# EE311_Example_Boost_Sch.net
KiCad netlist of a schematic drawn in Altium Designer
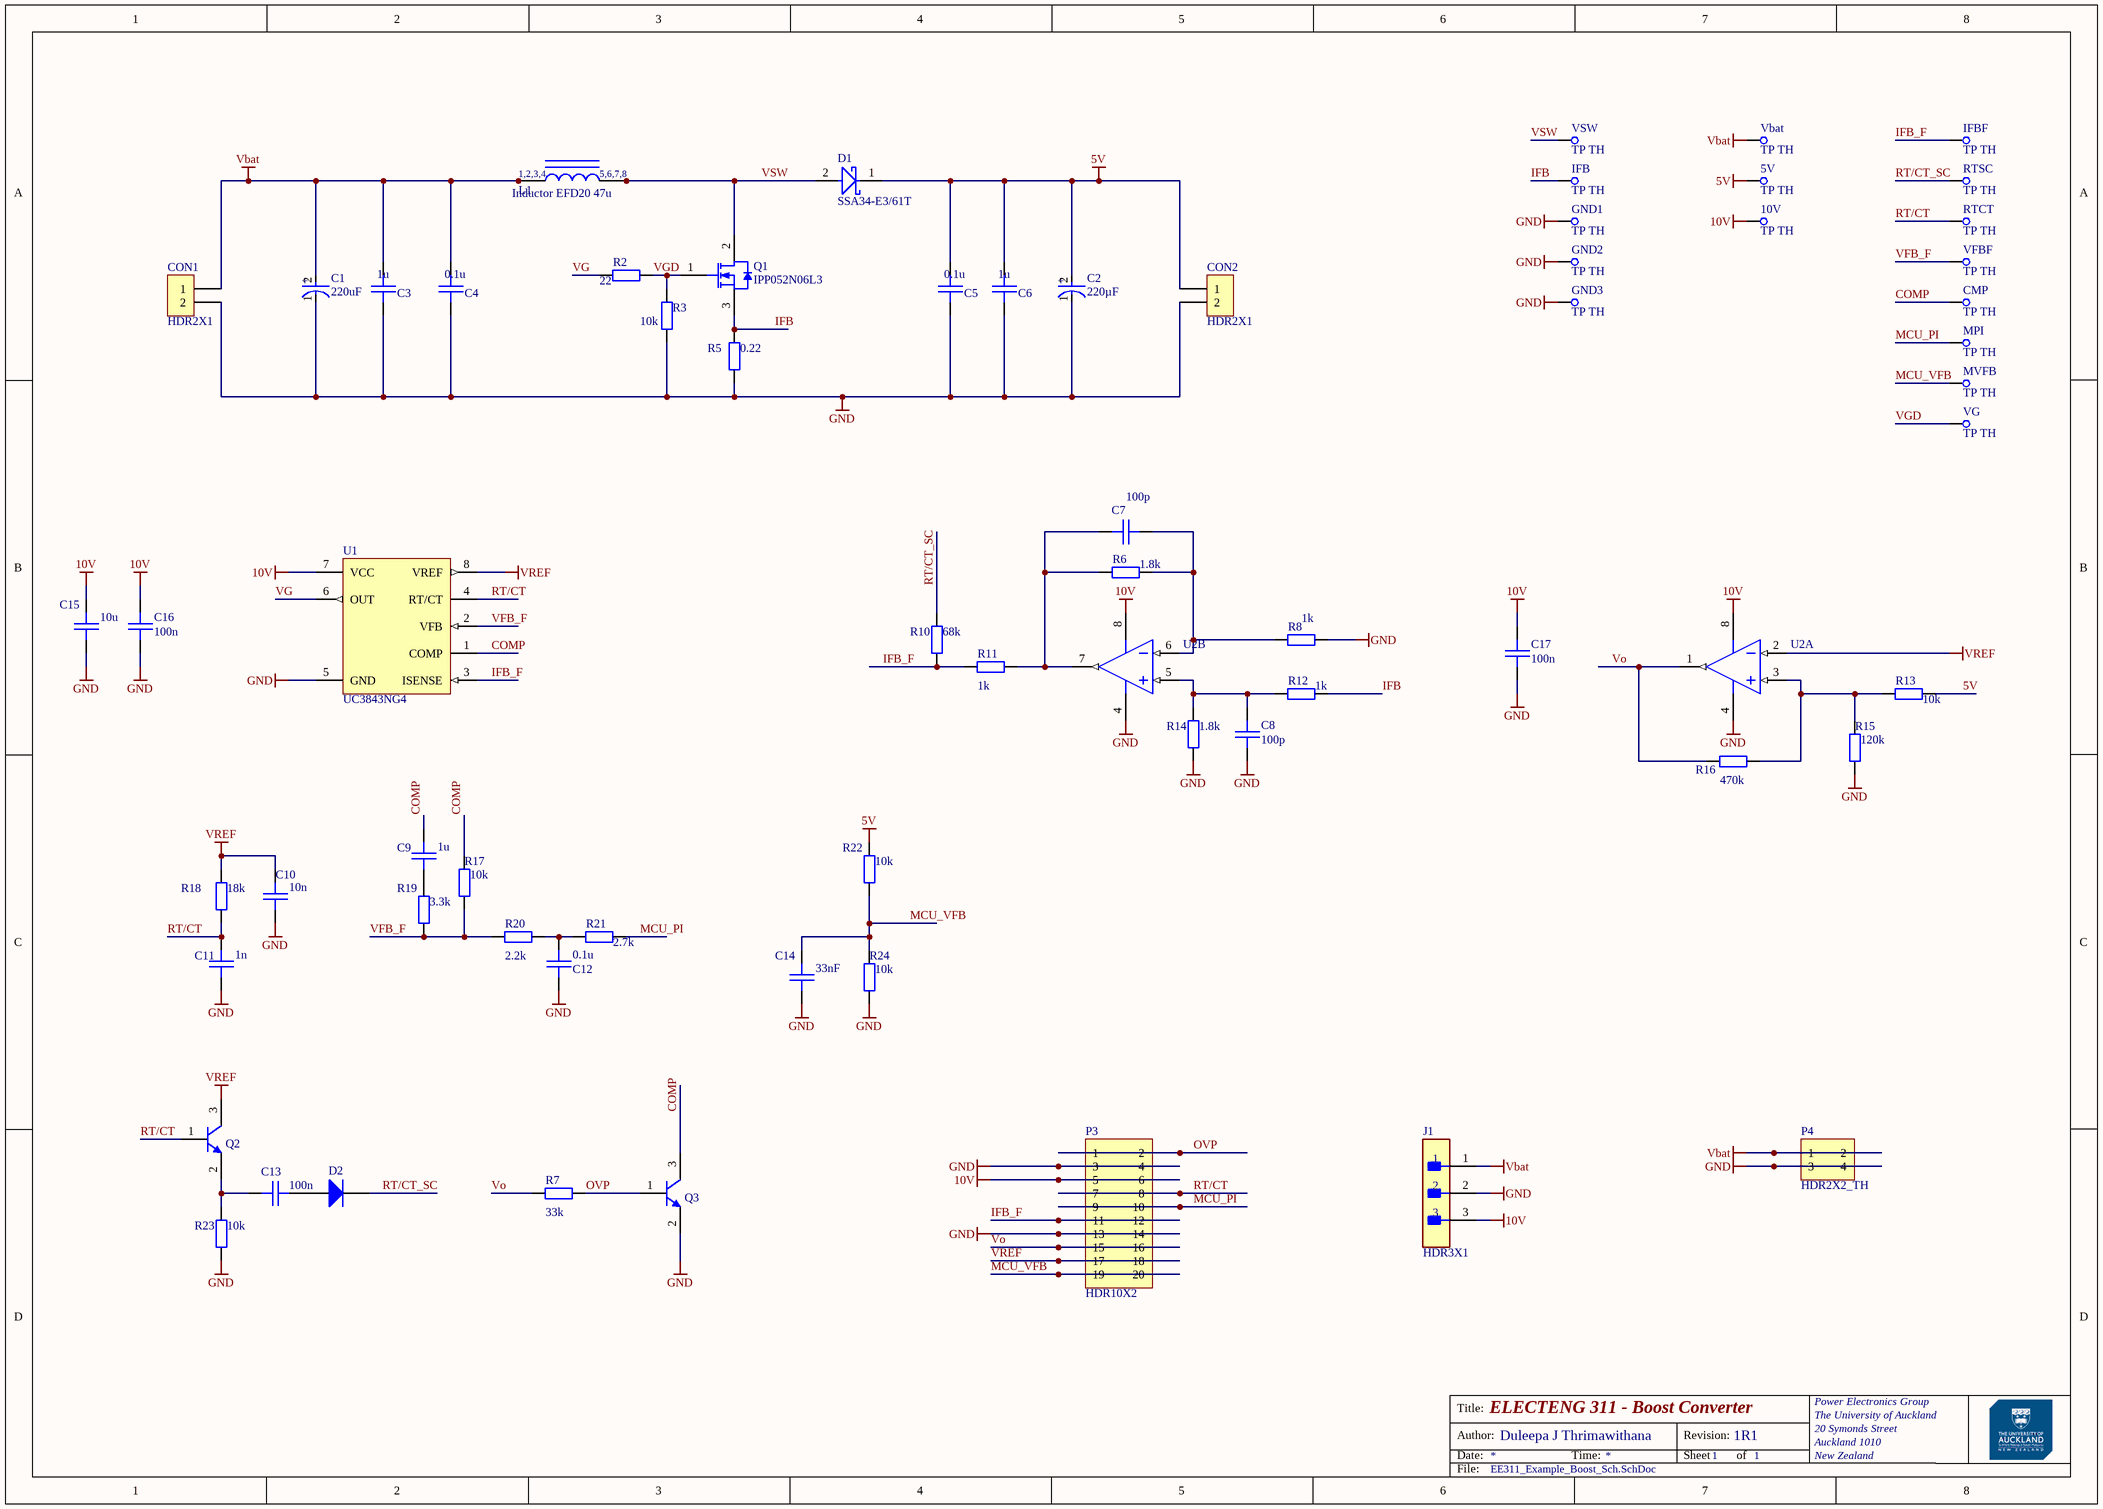
[diagram p0: EE311_Example_Boost_Sch.SchDoc]

(export (version "E")
  (design (tool "Eeschema 10.0.6"))
  (components
    (comp (ref "5V") (value "TP TH") (footprint "TP_TH_2.5mm") (libsource (lib "ECSE@UoA") (part "TP TH")))
    (comp (ref "10V") (value "TP TH") (footprint "TP_TH_2.5mm") (libsource (lib "ECSE@UoA") (part "TP TH")))
    (comp (ref "C1")
      (value "220uF")
      (footprint "FP-FKF-MFG")
      (fields (field (name "Comment") "EEE-FK1K330P"))
      (libsource (lib "ECSE@UoA") (part "a00bbbee19879c290e62620ae7e47b1"))
    )
    (comp (ref "C2")
      (value "220µF")
      (footprint "FP-FKF-MFG")
      (fields (field (name "Comment") "EEE-FK1K330P"))
      (libsource (lib "ECSE@UoA") (part "a00bbbee19879c290e62620ae7e47b1"))
    )
    (comp (ref "C3")
      (value "1u")
      (footprint "C1210")
      (description "Capacitor 1210")
      (libsource (lib "") (part "Symbol_1"))
    )
    (comp (ref "C4")
      (value "0.1u")
      (footprint "C1210")
      (description "Capacitor 1210")
      (libsource (lib "") (part "Symbol_1"))
    )
    (comp (ref "C5")
      (value "0.1u")
      (footprint "C1210")
      (description "Capacitor 1210")
      (libsource (lib "") (part "Symbol_1"))
    )
    (comp (ref "C6")
      (value "1u")
      (footprint "C1210")
      (description "Capacitor 1210")
      (libsource (lib "") (part "Symbol_1"))
    )
    (comp (ref "C7")
      (value "100p")
      (footprint "C0805")
      (description "Capacitor 0805")
      (fields (field (name "Comment") "CCAP0805"))
      (libsource (lib "") (part "Symbol_1"))
    )
    (comp (ref "C8")
      (value "100p")
      (footprint "C0805")
      (description "Capacitor 0805")
      (fields (field (name "Comment") "CCAP0805"))
      (libsource (lib "") (part "Symbol_1"))
    )
    (comp (ref "C9")
      (value "1u")
      (footprint "C0805")
      (description "Capacitor 0805")
      (fields (field (name "Comment") "CCAP0805"))
      (libsource (lib "") (part "Symbol_1"))
    )
    (comp (ref "C10")
      (value "10n")
      (footprint "C0805")
      (description "Capacitor 0805")
      (fields (field (name "Comment") "CCAP0805"))
      (libsource (lib "") (part "Symbol_1"))
    )
    (comp (ref "C11")
      (value "1n")
      (footprint "C0805")
      (description "Capacitor 0805")
      (fields (field (name "Comment") "CCAP0805"))
      (libsource (lib "") (part "Symbol_1"))
    )
    (comp (ref "C12")
      (value "0.1u")
      (footprint "C0805")
      (description "Capacitor 0805")
      (fields (field (name "Comment") "CCAP0805"))
      (libsource (lib "") (part "Symbol_1"))
    )
    (comp (ref "C13")
      (value "100n")
      (footprint "C0805")
      (description "Capacitor 0805")
      (fields (field (name "Comment") "CCAP0805"))
      (libsource (lib "") (part "Symbol_1"))
    )
    (comp (ref "C14")
      (value "33nF")
      (footprint "C0805")
      (description "Capacitor 0805")
      (fields (field (name "Comment") "CCAP0805"))
      (libsource (lib "") (part "Symbol_1"))
    )
    (comp (ref "C15")
      (value "10u")
      (footprint "C0805")
      (description "Capacitor 0805")
      (fields (field (name "Comment") "CCAP0805"))
      (libsource (lib "") (part "Symbol_1"))
    )
    (comp (ref "C16")
      (value "100n")
      (footprint "C0805")
      (description "Capacitor 0805")
      (fields (field (name "Comment") "CCAP0805"))
      (libsource (lib "") (part "Symbol_1"))
    )
    (comp (ref "C17")
      (value "100n")
      (footprint "C0805")
      (description "Capacitor 0805")
      (fields (field (name "Comment") "CCAP0805"))
      (libsource (lib "") (part "Symbol_1"))
    )
    (comp (ref "CMP") (value "TP TH") (footprint "TP_TH_2.5mm") (libsource (lib "ECSE@UoA") (part "TP TH")))
    (comp (ref "CON1")
      (value "HDR2X1")
      (footprint "HDR2X1_2P54")
      (description "Header 2X1")
      (libsource (lib "ECSE@UoA") (part "HDR2X1"))
    )
    (comp (ref "CON2")
      (value "HDR2X1")
      (footprint "HDR2X1_2P54")
      (description "Header 2X1")
      (libsource (lib "") (part "HDR2X1_1"))
    )
    (comp (ref "D1")
      (value "SSA34-E3/61T")
      (footprint "FP-95400-MFG")
      (description "Rectifier Diode, Schottky, 1 Phase, 1 Element, 3A, 40V V(RRM), Silicon, DO-214AC")
      (libsource (lib "ECSE@UoA") (part "1d6ec82d83fb6aee721767c19dac4b9"))
    )
    (comp (ref "D2")
      (value "1N4148_SMT_SOD123")
      (footprint "SOD123")
      (description "DIODE GEN PURP 100V 300MA SOD123")
      (fields
        (field (name "MANUFACTURER PART NUMBER") "1N4148W-13-F")
        (field (name "BASE PART NUMBER") "1N4148W")
      )
      (libsource (lib "ECSE@UoA") (part "1N4148_SMT_SOD123"))
    )
    (comp (ref "GND1") (value "TP TH") (footprint "TP_TH_3mm") (libsource (lib "ECSE@UoA") (part "TP TH")))
    (comp (ref "GND2") (value "TP TH") (footprint "TP_TH_3mm") (libsource (lib "ECSE@UoA") (part "TP TH")))
    (comp (ref "GND3") (value "TP TH") (footprint "TP_TH_3mm") (libsource (lib "ECSE@UoA") (part "TP TH")))
    (comp (ref "IFB") (value "TP TH") (footprint "TP_TH_3mm") (libsource (lib "ECSE@UoA") (part "TP TH")))
    (comp (ref "IFBF") (value "TP TH") (footprint "TP_TH_2.5mm") (libsource (lib "ECSE@UoA") (part "TP TH")))
    (comp (ref "J1")
      (value "HDR3X1")
      (footprint "FP-22-28-4035-MFG")
      (libsource (lib "ECSE@UoA") (part "0d3f023dd272f625e17a2be33dea85f"))
    )
    (comp (ref "L1")
      (value "Inductor EFD20 47u")
      (footprint "EFD20")
      (description "Inductor with core")
      (libsource (lib "ECSE@UoA") (part "Inductor EFD20"))
    )
    (comp (ref "MPI") (value "TP TH") (footprint "TP_TH_2.5mm") (libsource (lib "ECSE@UoA") (part "TP TH")))
    (comp (ref "MVFB") (value "TP TH") (footprint "TP_TH_2.5mm") (libsource (lib "ECSE@UoA") (part "TP TH")))
    (comp (ref "P3")
      (value "HDR10X2")
      (footprint "HDR10X2_2P54")
      (description "Header, 10-Pin, Dual row")
      (libsource (lib "ECSE@UoA") (part "HDR10X2"))
    )
    (comp (ref "P4")
      (value "HDR2X2_TH")
      (footprint "HDR2X2_2P54_Male")
      (description "Male Header, 4-Pin, Dual row")
      (libsource (lib "ECSE@UoA") (part "HDR2X2"))
    )
    (comp (ref "Q1")
      (value "IPP052N06L3")
      (footprint "TO220VH")
      (fields (field (name "MANUFACTURER") "Infineon") (field (name "PARTNUMBER") "IPP052N06L3 G"))
      (libsource (lib "ECSE@UoA") (part "IPP052N06L3"))
    )
    (comp (ref "Q2")
      (value "MMBT2222A")
      (footprint "SOT23SM")
      (description "General Purpose Transistor, NPN Silicon, 3-Pin SOT-23, Pb-Free, Tape and Reel")
      (fields (field (name "PARTNUMBER") "MMBT2222ALT1G") (field (name "MANUFACTURER") "On Semiconductor"))
      (libsource (lib "ECSE@UoA") (part "MMBT2222A"))
    )
    (comp (ref "Q3")
      (value "MMBT2222A")
      (footprint "SOT23SM")
      (description "General Purpose Transistor, NPN Silicon, 3-Pin SOT-23, Pb-Free, Tape and Reel")
      (fields (field (name "PARTNUMBER") "MMBT2222ALT1G") (field (name "MANUFACTURER") "On Semiconductor"))
      (libsource (lib "ECSE@UoA") (part "MMBT2222A"))
    )
    (comp (ref "R2")
      (value "22")
      (footprint "R0805")
      (description "Resistor 0805")
      (fields (field (name "Comment") "RES0805"))
      (libsource (lib "") (part "Symbol_3"))
    )
    (comp (ref "R3")
      (value "10k")
      (footprint "R0805")
      (description "Resistor 0805")
      (fields (field (name "Comment") "RES0805"))
      (libsource (lib "") (part "Symbol_2"))
    )
    (comp (ref "R5")
      (value "0.22")
      (footprint "R1210")
      (description "Resistor 1210")
      (fields (field (name "Comment") "RES1210"))
      (libsource (lib "") (part "Symbol_2"))
    )
    (comp (ref "R6")
      (value "1.8k")
      (footprint "R0805")
      (description "Resistor 0805")
      (fields (field (name "Comment") "RES0805"))
      (libsource (lib "") (part "Symbol_2"))
    )
    (comp (ref "R7")
      (value "33k")
      (footprint "R0805")
      (description "Resistor 0805")
      (fields (field (name "Comment") "RES0805"))
      (libsource (lib "") (part "Symbol_2"))
    )
    (comp (ref "R8")
      (value "1k")
      (footprint "R0805")
      (description "Resistor 0805")
      (fields (field (name "Comment") "RES0805"))
      (libsource (lib "") (part "Symbol_2"))
    )
    (comp (ref "R10")
      (value "68k")
      (footprint "R0805")
      (description "Resistor 0805")
      (fields (field (name "Comment") "RES0805"))
      (libsource (lib "ECSE@UoA") (part "Symbol"))
    )
    (comp (ref "R11")
      (value "1k")
      (footprint "R0805")
      (description "Resistor 0805")
      (fields (field (name "Comment") "RES0805"))
      (libsource (lib "") (part "Symbol_2"))
    )
    (comp (ref "R12")
      (value "1k")
      (footprint "R0805")
      (description "Resistor 0805")
      (fields (field (name "Comment") "RES0805"))
      (libsource (lib "") (part "Symbol_2"))
    )
    (comp (ref "R13")
      (value "10k")
      (footprint "R0805")
      (description "Resistor 0805")
      (fields (field (name "Comment") "RES0805"))
      (libsource (lib "") (part "Symbol_2"))
    )
    (comp (ref "R14")
      (value "1.8k")
      (footprint "R0805")
      (description "Resistor 0805")
      (fields (field (name "Comment") "RES0805"))
      (libsource (lib "") (part "Symbol_3"))
    )
    (comp (ref "R15")
      (value "120k")
      (footprint "R0805")
      (description "Resistor 0805")
      (fields (field (name "Comment") "RES0805"))
      (libsource (lib "") (part "Symbol_3"))
    )
    (comp (ref "R16")
      (value "470k")
      (footprint "R0805")
      (description "Resistor 0805")
      (fields (field (name "Comment") "RES0805"))
      (libsource (lib "") (part "Symbol_2"))
    )
    (comp (ref "R17")
      (value "10k")
      (footprint "R0805")
      (description "Resistor 0805")
      (fields (field (name "Comment") "RES0805"))
      (libsource (lib "") (part "Symbol_2"))
    )
    (comp (ref "R18")
      (value "18k")
      (footprint "R0805")
      (description "Resistor 0805")
      (fields (field (name "Comment") "RES0805"))
      (libsource (lib "") (part "Symbol_2"))
    )
    (comp (ref "R19")
      (value "3.3k")
      (footprint "R0805")
      (description "Resistor 0805")
      (fields (field (name "Comment") "RES0805"))
      (libsource (lib "") (part "Symbol_2"))
    )
    (comp (ref "R20")
      (value "2.2k")
      (footprint "R0805")
      (description "Resistor 0805")
      (fields (field (name "Comment") "RES0805"))
      (libsource (lib "ECSE@UoA") (part "Symbol"))
    )
    (comp (ref "R21")
      (value "2.7k")
      (footprint "R0805")
      (description "Resistor 0805")
      (fields (field (name "Comment") "RES0805"))
      (libsource (lib "ECSE@UoA") (part "Symbol"))
    )
    (comp (ref "R22")
      (value "10k")
      (footprint "R0805")
      (description "Resistor 0805")
      (fields (field (name "Comment") "RES0805"))
      (libsource (lib "") (part "Symbol_2"))
    )
    (comp (ref "R23")
      (value "10k")
      (footprint "R0805")
      (description "Resistor 0805")
      (fields (field (name "Comment") "RES0805"))
      (libsource (lib "ECSE@UoA") (part "Symbol"))
    )
    (comp (ref "R24")
      (value "10k")
      (footprint "R0805")
      (description "Resistor 0805")
      (fields (field (name "Comment") "RES0805"))
      (libsource (lib "") (part "Symbol_2"))
    )
    (comp (ref "RTCT") (value "TP TH") (footprint "TP_TH_2.5mm") (libsource (lib "ECSE@UoA") (part "TP TH")))
    (comp (ref "RTSC") (value "TP TH") (footprint "TP_TH_2.5mm") (libsource (lib "ECSE@UoA") (part "TP TH")))
    (comp (ref "U1")
      (value "UC3843NG4")
      (footprint "DIP-8")
      (libsource (lib "ECSE@UoA") (part "TI-UC3843P8"))
    )
    (comp (ref "U2")
      (value "LT6221")
      (footprint "SOIC8")
      (description "IC OPAMP LT6221 DUAL SM")
      (libsource (lib "ECSE@UoA") (part "LT6221"))
    )
    (comp (ref "Vbat") (value "TP TH") (footprint "TP_TH_2.5mm") (libsource (lib "ECSE@UoA") (part "TP TH")))
    (comp (ref "VFBF") (value "TP TH") (footprint "TP_TH_2.5mm") (libsource (lib "ECSE@UoA") (part "TP TH")))
    (comp (ref "VG") (value "TP TH") (footprint "TP_TH_2.5mm") (libsource (lib "ECSE@UoA") (part "TP TH")))
    (comp (ref "VSW") (value "TP TH") (footprint "TP_TH_3mm") (libsource (lib "ECSE@UoA") (part "TP TH")))
  )
  (nets
    (net (code "1") (name "/COMP") (class "Default")
      (node (ref "C9") (pin "1") (pinfunction "1_1") (pintype "passive"))
      (node (ref "CMP") (pin "1") (pinfunction "1_1") (pintype "passive"))
      (node (ref "Q3") (pin "3") (pinfunction "C_3") (pintype "passive"))
      (node (ref "R17") (pin "2") (pinfunction "2_2") (pintype "passive"))
      (node (ref "U1") (pin "1") (pinfunction "COMP_1") (pintype "passive"))
    )
    (net (code "2") (name "/IFB") (class "Default")
      (node (ref "IFB") (pin "1") (pinfunction "1_1") (pintype "passive"))
      (node (ref "Q1") (pin "3") (pinfunction "SOURCE_3") (pintype "passive"))
      (node (ref "R12") (pin "2") (pinfunction "2_2") (pintype "passive"))
      (node (ref "R5") (pin "2") (pinfunction "2_2") (pintype "passive"))
    )
    (net (code "3") (name "/IFB_F") (class "Default")
      (node (ref "IFBF") (pin "1") (pinfunction "1_1") (pintype "passive"))
      (node (ref "P3") (pin "11") (pinfunction "11_11") (pintype "passive"))
      (node (ref "P3") (pin "12") (pinfunction "12_12") (pintype "passive"))
      (node (ref "R10") (pin "2") (pinfunction "2_2") (pintype "passive"))
      (node (ref "R11") (pin "1") (pinfunction "1_1") (pintype "passive"))
      (node (ref "U1") (pin "3") (pinfunction "ISENSE_3") (pintype "input"))
    )
    (net (code "4") (name "/MCU_PI") (class "Default")
      (node (ref "MPI") (pin "1") (pinfunction "1_1") (pintype "passive"))
      (node (ref "P3") (pin "10") (pinfunction "10_10") (pintype "passive"))
      (node (ref "P3") (pin "9") (pinfunction "9_9") (pintype "passive"))
      (node (ref "R21") (pin "1") (pinfunction "1_1") (pintype "passive"))
    )
    (net (code "5") (name "/MCU_VFB") (class "Default")
      (node (ref "C14") (pin "1") (pinfunction "1_1") (pintype "passive"))
      (node (ref "MVFB") (pin "1") (pinfunction "1_1") (pintype "passive"))
      (node (ref "P3") (pin "19") (pinfunction "19_19") (pintype "passive"))
      (node (ref "P3") (pin "20") (pinfunction "20_20") (pintype "passive"))
      (node (ref "R22") (pin "1") (pinfunction "1_1") (pintype "passive"))
      (node (ref "R24") (pin "2") (pinfunction "2_2") (pintype "passive"))
    )
    (net (code "6") (name "/OVP") (class "Default")
      (node (ref "P3") (pin "1") (pinfunction "1_1") (pintype "passive"))
      (node (ref "P3") (pin "2") (pinfunction "2_2") (pintype "passive"))
      (node (ref "Q3") (pin "1") (pinfunction "B_1") (pintype "passive"))
      (node (ref "R7") (pin "2") (pinfunction "2_2") (pintype "passive"))
    )
    (net (code "7") (name "/RT{slash}CT") (class "Default")
      (node (ref "C11") (pin "1") (pinfunction "1_1") (pintype "passive"))
      (node (ref "P3") (pin "7") (pinfunction "7_7") (pintype "passive"))
      (node (ref "P3") (pin "8") (pinfunction "8_8") (pintype "passive"))
      (node (ref "Q2") (pin "1") (pinfunction "B_1") (pintype "passive"))
      (node (ref "R18") (pin "1") (pinfunction "1_1") (pintype "passive"))
      (node (ref "RTCT") (pin "1") (pinfunction "1_1") (pintype "passive"))
      (node (ref "U1") (pin "4") (pinfunction "RT/CT_4") (pintype "passive"))
    )
    (net (code "8") (name "/RT{slash}CT_SC") (class "Default")
      (node (ref "D2") (pin "2") (pinfunction "K_2") (pintype "passive"))
      (node (ref "R10") (pin "1") (pinfunction "1_1") (pintype "passive"))
      (node (ref "RTSC") (pin "1") (pinfunction "1_1") (pintype "passive"))
    )
    (net (code "9") (name "/VFB_F") (class "Default")
      (node (ref "R17") (pin "1") (pinfunction "1_1") (pintype "passive"))
      (node (ref "R19") (pin "1") (pinfunction "1_1") (pintype "passive"))
      (node (ref "R20") (pin "2") (pinfunction "2_2") (pintype "passive"))
      (node (ref "U1") (pin "2") (pinfunction "VFB_2") (pintype "input"))
      (node (ref "VFBF") (pin "1") (pinfunction "1_1") (pintype "passive"))
    )
    (net (code "10") (name "/VG") (class "Default")
      (node (ref "R2") (pin "1") (pinfunction "1_1") (pintype "passive"))
      (node (ref "U1") (pin "6") (pinfunction "OUT_6") (pintype "output"))
    )
    (net (code "11") (name "/VGD") (class "Default")
      (node (ref "Q1") (pin "1") (pinfunction "GATE_1") (pintype "passive"))
      (node (ref "R2") (pin "2") (pinfunction "2_2") (pintype "passive"))
      (node (ref "R3") (pin "2") (pinfunction "2_2") (pintype "passive"))
      (node (ref "VG") (pin "1") (pinfunction "1_1") (pintype "passive"))
    )
    (net (code "12") (name "/VSW") (class "Default")
      (node (ref "D1") (pin "2") (pinfunction "A_2") (pintype "passive"))
      (node (ref "L1") (pin "5") (pinfunction "5_5") (pintype "passive"))
      (node (ref "L1") (pin "6") (pinfunction "6_6") (pintype "passive"))
      (node (ref "L1") (pin "7") (pinfunction "7_7") (pintype "passive"))
      (node (ref "L1") (pin "8") (pinfunction "8_8") (pintype "passive"))
      (node (ref "Q1") (pin "2") (pinfunction "DRAIN_2") (pintype "passive"))
      (node (ref "VSW") (pin "1") (pinfunction "1_1") (pintype "passive"))
    )
    (net (code "13") (name "/Vo") (class "Default")
      (node (ref "P3") (pin "15") (pinfunction "15_15") (pintype "passive"))
      (node (ref "P3") (pin "16") (pinfunction "16_16") (pintype "passive"))
      (node (ref "R16") (pin "1") (pinfunction "1_1") (pintype "passive"))
      (node (ref "R7") (pin "1") (pinfunction "1_1") (pintype "passive"))
      (node (ref "U2") (pin "1") (pinfunction "OUT1_1") (pintype "output"))
    )
    (net (code "14") (name "5V") (class "Default")
      (node (ref "5V") (pin "1") (pinfunction "1_1") (pintype "passive"))
      (node (ref "C2") (pin "2") (pinfunction "A_2") (pintype "passive"))
      (node (ref "C5") (pin "2") (pinfunction "2_2") (pintype "passive"))
      (node (ref "C6") (pin "2") (pinfunction "2_2") (pintype "passive"))
      (node (ref "CON2") (pin "1") (pinfunction "1_1") (pintype "passive"))
      (node (ref "D1") (pin "1") (pinfunction "C_1") (pintype "passive"))
      (node (ref "R13") (pin "2") (pinfunction "2_2") (pintype "passive"))
      (node (ref "R22") (pin "2") (pinfunction "2_2") (pintype "passive"))
    )
    (net (code "15") (name "10V") (class "Default")
      (node (ref "10V") (pin "1") (pinfunction "1_1") (pintype "passive"))
      (node (ref "C15") (pin "1") (pinfunction "1_1") (pintype "passive"))
      (node (ref "C16") (pin "1") (pinfunction "1_1") (pintype "passive"))
      (node (ref "C17") (pin "1") (pinfunction "1_1") (pintype "passive"))
      (node (ref "J1") (pin "3") (pinfunction "3_3") (pintype "passive"))
      (node (ref "P3") (pin "5") (pinfunction "5_5") (pintype "passive"))
      (node (ref "P3") (pin "6") (pinfunction "6_6") (pintype "passive"))
      (node (ref "U1") (pin "7") (pinfunction "VCC_7") (pintype "power_in"))
      (node (ref "U2") (pin "8") (pinfunction "VDD_8") (pintype "power_in"))
    )
    (net (code "16") (name "GND") (class "Default")
      (node (ref "C1") (pin "1") (pinfunction "C_1") (pintype "passive"))
      (node (ref "C10") (pin "2") (pinfunction "2_2") (pintype "passive"))
      (node (ref "C11") (pin "2") (pinfunction "2_2") (pintype "passive"))
      (node (ref "C12") (pin "2") (pinfunction "2_2") (pintype "passive"))
      (node (ref "C14") (pin "2") (pinfunction "2_2") (pintype "passive"))
      (node (ref "C15") (pin "2") (pinfunction "2_2") (pintype "passive"))
      (node (ref "C16") (pin "2") (pinfunction "2_2") (pintype "passive"))
      (node (ref "C17") (pin "2") (pinfunction "2_2") (pintype "passive"))
      (node (ref "C2") (pin "1") (pinfunction "C_1") (pintype "passive"))
      (node (ref "C3") (pin "1") (pinfunction "1_1") (pintype "passive"))
      (node (ref "C4") (pin "1") (pinfunction "1_1") (pintype "passive"))
      (node (ref "C5") (pin "1") (pinfunction "1_1") (pintype "passive"))
      (node (ref "C6") (pin "1") (pinfunction "1_1") (pintype "passive"))
      (node (ref "C8") (pin "2") (pinfunction "2_2") (pintype "passive"))
      (node (ref "CON1") (pin "2") (pinfunction "2_2") (pintype "passive"))
      (node (ref "CON2") (pin "2") (pinfunction "2_2") (pintype "passive"))
      (node (ref "GND1") (pin "1") (pinfunction "1_1") (pintype "passive"))
      (node (ref "GND2") (pin "1") (pinfunction "1_1") (pintype "passive"))
      (node (ref "GND3") (pin "1") (pinfunction "1_1") (pintype "passive"))
      (node (ref "J1") (pin "2") (pinfunction "2_2") (pintype "passive"))
      (node (ref "P3") (pin "13") (pinfunction "13_13") (pintype "passive"))
      (node (ref "P3") (pin "14") (pinfunction "14_14") (pintype "passive"))
      (node (ref "P3") (pin "3") (pinfunction "3_3") (pintype "passive"))
      (node (ref "P3") (pin "4") (pinfunction "4_4") (pintype "passive"))
      (node (ref "P4") (pin "3") (pinfunction "3_3") (pintype "passive"))
      (node (ref "P4") (pin "4") (pinfunction "4_4") (pintype "passive"))
      (node (ref "Q3") (pin "2") (pinfunction "E_2") (pintype "passive"))
      (node (ref "R14") (pin "1") (pinfunction "1_1") (pintype "passive"))
      (node (ref "R15") (pin "1") (pinfunction "1_1") (pintype "passive"))
      (node (ref "R23") (pin "2") (pinfunction "2_2") (pintype "passive"))
      (node (ref "R24") (pin "1") (pinfunction "1_1") (pintype "passive"))
      (node (ref "R3") (pin "1") (pinfunction "1_1") (pintype "passive"))
      (node (ref "R5") (pin "1") (pinfunction "1_1") (pintype "passive"))
      (node (ref "R8") (pin "2") (pinfunction "2_2") (pintype "passive"))
      (node (ref "U1") (pin "5") (pinfunction "GND_5") (pintype "power_in"))
      (node (ref "U2") (pin "4") (pinfunction "GND_4") (pintype "power_in"))
    )
    (net (code "17") (name "Net-(C9-Pad2)") (class "Default")
      (node (ref "C9") (pin "2") (pinfunction "2_2") (pintype "passive"))
      (node (ref "R19") (pin "2") (pinfunction "2_2") (pintype "passive"))
    )
    (net (code "18") (name "Net-(C12-Pad1)") (class "Default")
      (node (ref "C12") (pin "1") (pinfunction "1_1") (pintype "passive"))
      (node (ref "R20") (pin "1") (pinfunction "1_1") (pintype "passive"))
      (node (ref "R21") (pin "2") (pinfunction "2_2") (pintype "passive"))
    )
    (net (code "19") (name "Net-(D2-A)") (class "Default")
      (node (ref "C13") (pin "2") (pinfunction "2_2") (pintype "passive"))
      (node (ref "D2") (pin "1") (pinfunction "A_1") (pintype "passive"))
    )
    (net (code "20") (name "Net-(Q2-E)") (class "Default")
      (node (ref "C13") (pin "1") (pinfunction "1_1") (pintype "passive"))
      (node (ref "Q2") (pin "2") (pinfunction "E_2") (pintype "passive"))
      (node (ref "R23") (pin "1") (pinfunction "1_1") (pintype "passive"))
    )
    (net (code "21") (name "Net-(U2A-IN1+)") (class "Default")
      (node (ref "R13") (pin "1") (pinfunction "1_1") (pintype "passive"))
      (node (ref "R15") (pin "2") (pinfunction "2_2") (pintype "passive"))
      (node (ref "R16") (pin "2") (pinfunction "2_2") (pintype "passive"))
      (node (ref "U2") (pin "3") (pinfunction "IN1+_3") (pintype "input"))
    )
    (net (code "22") (name "Net-(U2B-IN1+)") (class "Default")
      (node (ref "C8") (pin "1") (pinfunction "1_1") (pintype "passive"))
      (node (ref "R12") (pin "1") (pinfunction "1_1") (pintype "passive"))
      (node (ref "R14") (pin "2") (pinfunction "2_2") (pintype "passive"))
      (node (ref "U2") (pin "5") (pinfunction "IN1+_5") (pintype "input"))
    )
    (net (code "23") (name "Net-(U2B-IN1-)") (class "Default")
      (node (ref "C7") (pin "2") (pinfunction "2_2") (pintype "passive"))
      (node (ref "R6") (pin "2") (pinfunction "2_2") (pintype "passive"))
      (node (ref "R8") (pin "1") (pinfunction "1_1") (pintype "passive"))
      (node (ref "U2") (pin "6") (pinfunction "IN1-_6") (pintype "input"))
    )
    (net (code "24") (name "Net-(U2B-OUT1)") (class "Default")
      (node (ref "C7") (pin "1") (pinfunction "1_1") (pintype "passive"))
      (node (ref "R11") (pin "2") (pinfunction "2_2") (pintype "passive"))
      (node (ref "R6") (pin "1") (pinfunction "1_1") (pintype "passive"))
      (node (ref "U2") (pin "7") (pinfunction "OUT1_7") (pintype "output"))
    )
    (net (code "25") (name "VREF") (class "Default")
      (node (ref "C10") (pin "1") (pinfunction "1_1") (pintype "passive"))
      (node (ref "P3") (pin "17") (pinfunction "17_17") (pintype "passive"))
      (node (ref "P3") (pin "18") (pinfunction "18_18") (pintype "passive"))
      (node (ref "Q2") (pin "3") (pinfunction "C_3") (pintype "passive"))
      (node (ref "R18") (pin "2") (pinfunction "2_2") (pintype "passive"))
      (node (ref "U1") (pin "8") (pinfunction "VREF_8") (pintype "output"))
      (node (ref "U2") (pin "2") (pinfunction "IN1-_2") (pintype "input"))
    )
    (net (code "26") (name "Vbat") (class "Default")
      (node (ref "C1") (pin "2") (pinfunction "A_2") (pintype "passive"))
      (node (ref "C3") (pin "2") (pinfunction "2_2") (pintype "passive"))
      (node (ref "C4") (pin "2") (pinfunction "2_2") (pintype "passive"))
      (node (ref "CON1") (pin "1") (pinfunction "1_1") (pintype "passive"))
      (node (ref "J1") (pin "1") (pinfunction "1_1") (pintype "passive"))
      (node (ref "L1") (pin "1") (pinfunction "1_1") (pintype "passive"))
      (node (ref "L1") (pin "2") (pinfunction "2_2") (pintype "passive"))
      (node (ref "L1") (pin "3") (pinfunction "3_3") (pintype "passive"))
      (node (ref "L1") (pin "4") (pinfunction "4_4") (pintype "passive"))
      (node (ref "P4") (pin "1") (pinfunction "1_1") (pintype "passive"))
      (node (ref "P4") (pin "2") (pinfunction "2_2") (pintype "passive"))
      (node (ref "Vbat") (pin "1") (pinfunction "1_1") (pintype "passive"))
    )
  )
)
